# GyroMPU.net
KiCad netlist of a schematic drawn in Altium Designer
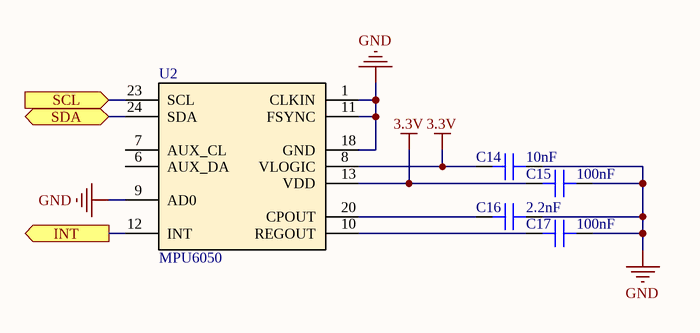
[diagram p0: GyroMPU.SchDoc]

(export (version "E")
  (design (tool "Eeschema 10.0.6"))
  (components
    (comp (ref "C14")
      (value "10nF")
      (footprint "CAP 0603_1608")
      (description "SMT Capacitor")
      (libsource (lib "Capacitor") (part "Cap 0603"))
    )
    (comp (ref "C15")
      (value "100nF")
      (footprint "CAP 0603_1608")
      (description "SMT Capacitor")
      (libsource (lib "Capacitor") (part "Cap 0603"))
    )
    (comp (ref "C16")
      (value "2.2nF")
      (footprint "CAP 0603_1608")
      (description "SMT Capacitor")
      (libsource (lib "Capacitor") (part "Cap 0603"))
    )
    (comp (ref "C17")
      (value "100nF")
      (footprint "CAP 0603_1608")
      (description "SMT Capacitor")
      (libsource (lib "Capacitor") (part "Cap 0603"))
    )
    (comp (ref "U2") (value "MPU6050") (footprint "QFN-24TA") (libsource (lib "Salman_lib") (part "MPU6050")))
  )
  (nets
    (net (code "1") (name "/INT") (class "Default")
      (node (ref "U2") (pin "12") (pinfunction "INT_12") (pintype "passive"))
    )
    (net (code "2") (name "/SCL") (class "Default")
      (node (ref "U2") (pin "23") (pinfunction "SCL_23") (pintype "passive"))
    )
    (net (code "3") (name "/SDA") (class "Default")
      (node (ref "U2") (pin "24") (pinfunction "SDA_24") (pintype "passive"))
    )
    (net (code "4") (name "3.3V") (class "Default")
      (node (ref "C14") (pin "2") (pinfunction "2_2") (pintype "passive"))
      (node (ref "C15") (pin "2") (pinfunction "2_2") (pintype "passive"))
      (node (ref "U2") (pin "13") (pinfunction "VDD_13") (pintype "passive"))
      (node (ref "U2") (pin "8") (pinfunction "VLOGIC_8") (pintype "passive"))
    )
    (net (code "5") (name "GND") (class "Default")
      (node (ref "C14") (pin "1") (pinfunction "1_1") (pintype "passive"))
      (node (ref "C15") (pin "1") (pinfunction "1_1") (pintype "passive"))
      (node (ref "C16") (pin "2") (pinfunction "2_2") (pintype "passive"))
      (node (ref "C17") (pin "2") (pinfunction "2_2") (pintype "passive"))
      (node (ref "U2") (pin "1") (pinfunction "CLKIN_1") (pintype "passive"))
      (node (ref "U2") (pin "11") (pinfunction "FSYNC_11") (pintype "passive"))
      (node (ref "U2") (pin "18") (pinfunction "GND_18") (pintype "passive"))
      (node (ref "U2") (pin "9") (pinfunction "AD0_9") (pintype "passive"))
    )
    (net (code "6") (name "Net-(U2-CPOUT)") (class "Default")
      (node (ref "C16") (pin "1") (pinfunction "1_1") (pintype "passive"))
      (node (ref "U2") (pin "20") (pinfunction "CPOUT_20") (pintype "passive"))
    )
    (net (code "7") (name "Net-(U2-REGOUT)") (class "Default")
      (node (ref "C17") (pin "1") (pinfunction "1_1") (pintype "passive"))
      (node (ref "U2") (pin "10") (pinfunction "REGOUT_10") (pintype "passive"))
    )
    (net (code "8") (name "unconnected-(U2-AUX_CL-Pad7)") (class "Default")
      (node (ref "U2") (pin "7") (pinfunction "AUX_CL_7") (pintype "passive"))
    )
    (net (code "9") (name "unconnected-(U2-AUX_DA-Pad6)") (class "Default")
      (node (ref "U2") (pin "6") (pinfunction "AUX_DA_6") (pintype "passive"))
    )
  )
)
